# demeter_v27.net
KiCad netlist of a schematic drawn in EAGLE
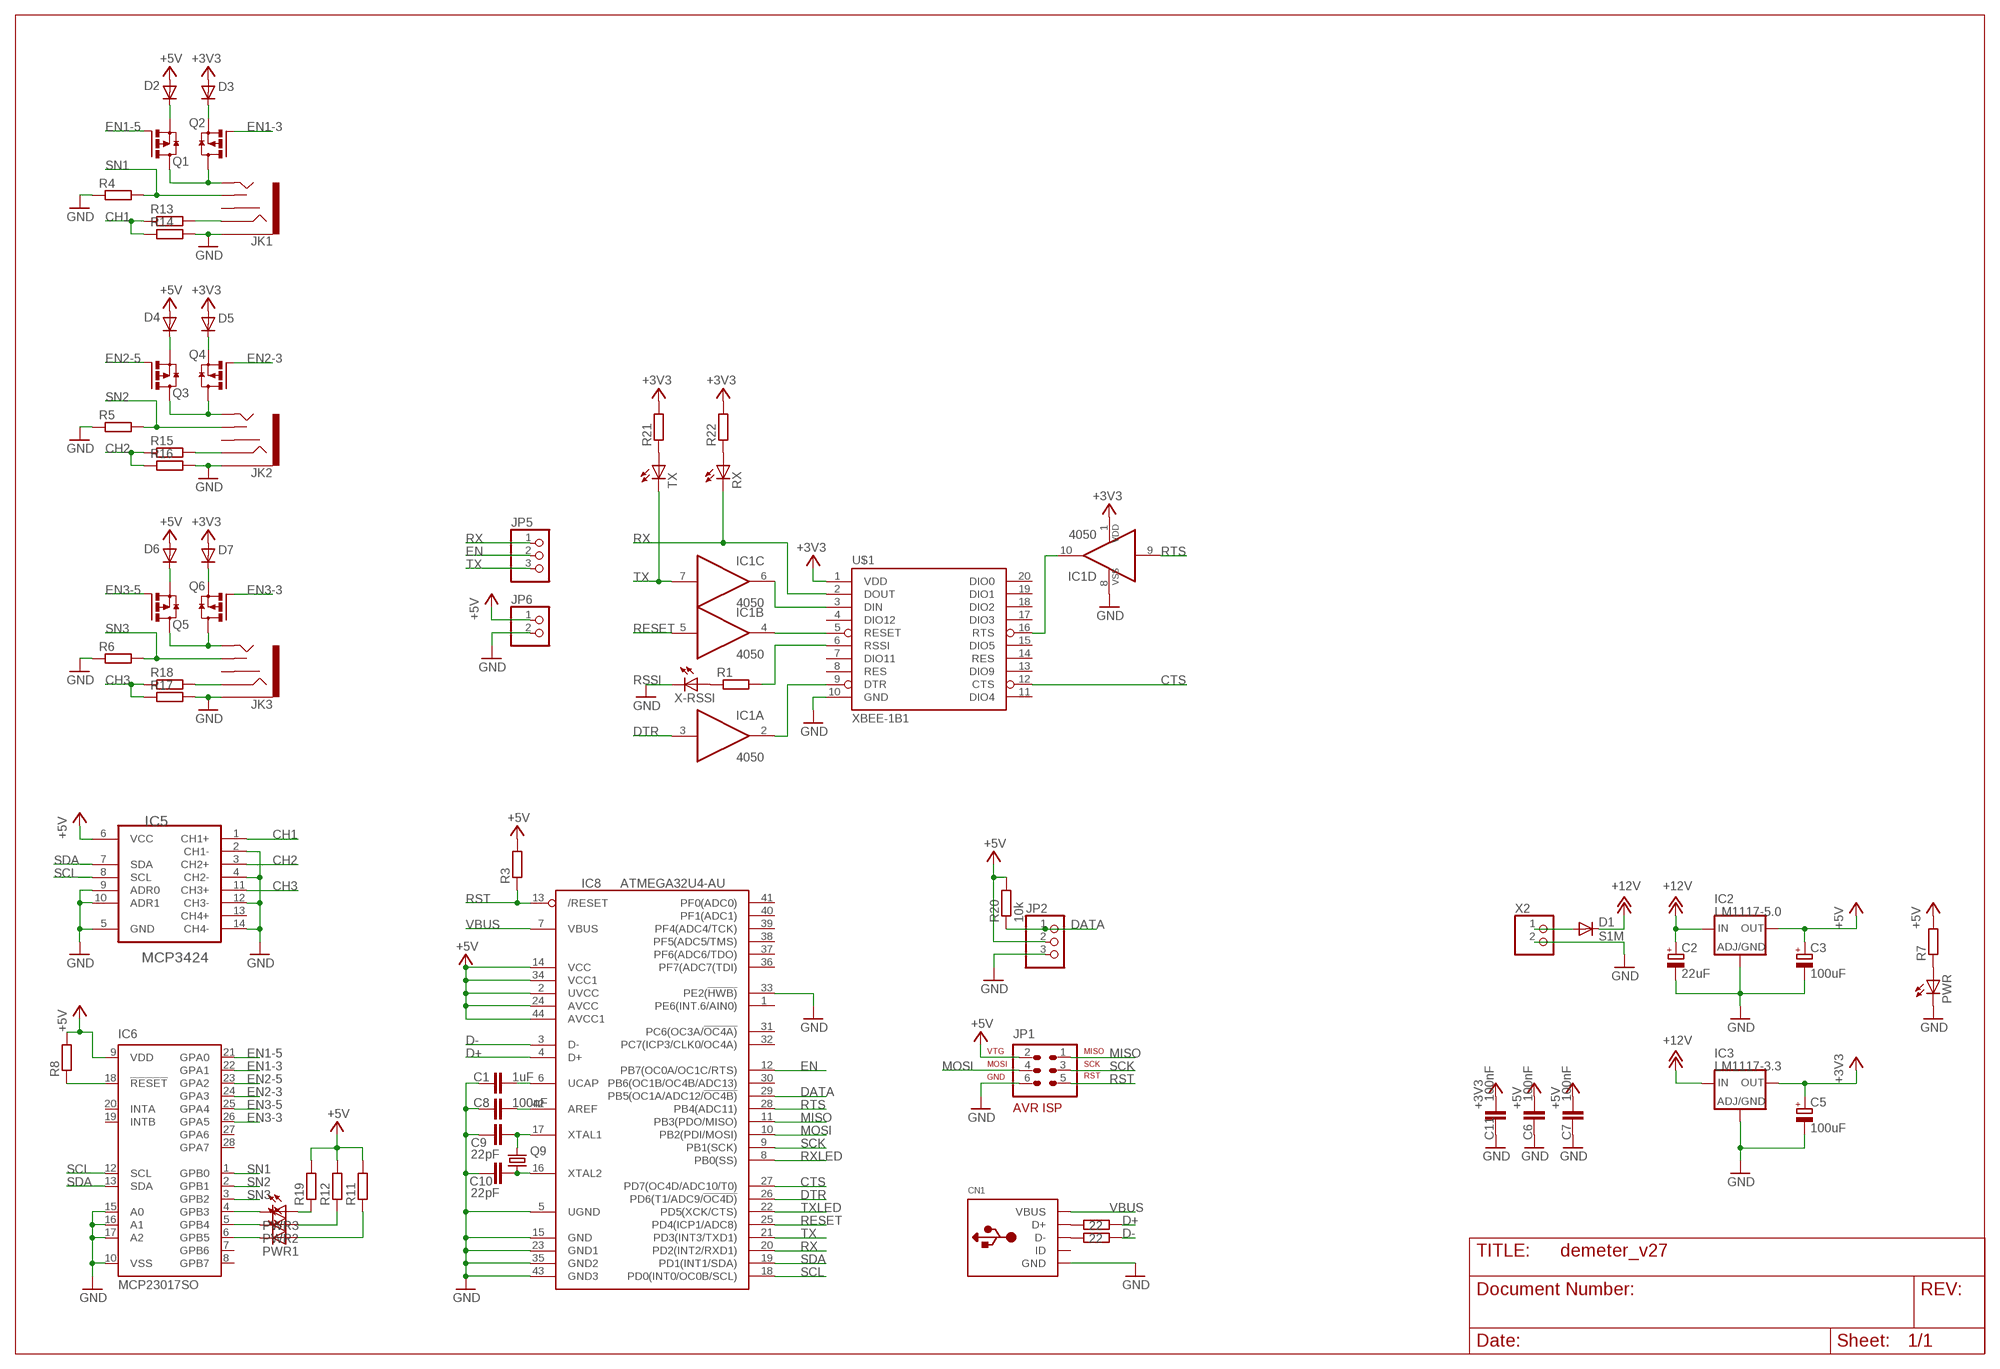
[diagram p0: schematic, sheet 1]

(export (version "E")
  (design (tool "Eeschema 10.0.6"))
  (components
    (comp (ref "C1")
      (value "1uF")
      (footprint "eagle-import:C0805K")
      (libsource (lib "eagle-import") (part "C-EUC0805K"))
    )
    (comp (ref "C2")
      (value "22uF")
      (footprint "eagle-import:PANASONIC_D")
      (libsource (lib "eagle-import") (part "CPOL-EUPD"))
    )
    (comp (ref "C3")
      (value "100uF")
      (footprint "eagle-import:PANASONIC_D")
      (libsource (lib "eagle-import") (part "CPOL-EUPD"))
    )
    (comp (ref "C5")
      (value "100uF")
      (footprint "eagle-import:PANASONIC_D")
      (libsource (lib "eagle-import") (part "CPOL-EUPD"))
    )
    (comp (ref "C6")
      (value "100nF")
      (footprint "eagle-import:C0805K")
      (libsource (lib "eagle-import") (part "C-EUC0805K"))
    )
    (comp (ref "C7")
      (value "100nF")
      (footprint "eagle-import:C0805K")
      (libsource (lib "eagle-import") (part "C-EUC0805K"))
    )
    (comp (ref "C8")
      (value "100nF")
      (footprint "eagle-import:C0805K")
      (libsource (lib "eagle-import") (part "C-EUC0805K"))
    )
    (comp (ref "C9")
      (value "22pF")
      (footprint "eagle-import:C0805K")
      (libsource (lib "eagle-import") (part "C-EUC0805K"))
    )
    (comp (ref "C10")
      (value "22pF")
      (footprint "eagle-import:C0805K")
      (libsource (lib "eagle-import") (part "C-EUC0805K"))
    )
    (comp (ref "C11")
      (value "100nF")
      (footprint "eagle-import:C0805K")
      (libsource (lib "eagle-import") (part "C-EUC0805K"))
    )
    (comp (ref "CN1")
      (value "USBMINIB")
      (footprint "eagle-import:USB-MINIB")
      (libsource (lib "eagle-import") (part "USBMINIB"))
    )
    (comp (ref "D1")
      (value "S1M")
      (footprint "eagle-import:DO-214AC")
      (libsource (lib "eagle-import") (part "S1M"))
    )
    (comp (ref "D2")
      (value "MBR0520")
      (footprint "eagle-import:SOD123")
      (libsource (lib "eagle-import") (part "MBR0520"))
    )
    (comp (ref "D3")
      (value "MBR0520")
      (footprint "eagle-import:SOD123")
      (libsource (lib "eagle-import") (part "MBR0520"))
    )
    (comp (ref "D4")
      (value "MBR0520")
      (footprint "eagle-import:SOD123")
      (libsource (lib "eagle-import") (part "MBR0520"))
    )
    (comp (ref "D5")
      (value "MBR0520")
      (footprint "eagle-import:SOD123")
      (libsource (lib "eagle-import") (part "MBR0520"))
    )
    (comp (ref "D6")
      (value "MBR0520")
      (footprint "eagle-import:SOD123")
      (libsource (lib "eagle-import") (part "MBR0520"))
    )
    (comp (ref "D7")
      (value "MBR0520")
      (footprint "eagle-import:SOD123")
      (libsource (lib "eagle-import") (part "MBR0520"))
    )
    (comp (ref "IC1")
      (value "4050")
      (footprint "eagle-import:SO16")
      (libsource (lib "eagle-import") (part "4050D"))
    )
    (comp (ref "IC2")
      (value "LM1117-5.0")
      (footprint "eagle-import:DPACK")
      (libsource (lib "eagle-import") (part "LM1117DT"))
    )
    (comp (ref "IC3")
      (value "LM1117-3.3")
      (footprint "eagle-import:DPACK")
      (libsource (lib "eagle-import") (part "LM1117DT"))
    )
    (comp (ref "IC5")
      (value "MCP3424")
      (footprint "eagle-import:SO14")
      (fields (field (name "MPN") "MCP3424-E/SL"))
      (libsource (lib "eagle-import") (part "MCP3424"))
    )
    (comp (ref "IC6")
      (value "MCP23017SO")
      (footprint "eagle-import:SO28W")
      (fields (field (name "MF") "MICROCHIP") (field (name "MPN") "MCP23017-E/SO"))
      (libsource (lib "eagle-import") (part "MCP23017SO"))
    )
    (comp (ref "IC8")
      (value "ATMEGA32U4-AU")
      (footprint "eagle-import:TQFP44")
      (libsource (lib "eagle-import") (part "ATMEGA32U4-AU"))
    )
    (comp (ref "JK1")
      (value "AUDIO-JACK2PTH")
      (footprint "eagle-import:AUDIO-JACK")
      (libsource (lib "eagle-import") (part "AUDIO-JACK2PTH"))
    )
    (comp (ref "JK2")
      (value "AUDIO-JACK2PTH")
      (footprint "eagle-import:AUDIO-JACK")
      (libsource (lib "eagle-import") (part "AUDIO-JACK2PTH"))
    )
    (comp (ref "JK3")
      (value "AUDIO-JACK2PTH")
      (footprint "eagle-import:AUDIO-JACK")
      (libsource (lib "eagle-import") (part "AUDIO-JACK2PTH"))
    )
    (comp (ref "JP1")
      (value "AVR-ISP-6")
      (footprint "eagle-import:AVR-ISP-6")
      (libsource (lib "eagle-import") (part "AVR-ISP-6"))
    )
    (comp (ref "JP2")
      (value "PINHD-1X3180")
      (footprint "eagle-import:1X03")
      (libsource (lib "eagle-import") (part "PINHD-1X3180"))
    )
    (comp (ref "JP5")
      (value "PINHD-1X3180")
      (footprint "eagle-import:1X03")
      (libsource (lib "eagle-import") (part "PINHD-1X3180"))
    )
    (comp (ref "JP6")
      (value "PINHD-1X2")
      (footprint "eagle-import:1X02")
      (libsource (lib "eagle-import") (part "PINHD-1X2"))
    )
    (comp (ref "PWR")
      (value "LED0805")
      (footprint "eagle-import:CHIP-LED0805")
      (libsource (lib "eagle-import") (part "LED0805"))
    )
    (comp (ref "PWR1")
      (value "LED0805")
      (footprint "eagle-import:CHIP-LED0805")
      (libsource (lib "eagle-import") (part "LED0805"))
    )
    (comp (ref "PWR2")
      (value "LED0805")
      (footprint "eagle-import:CHIP-LED0805")
      (libsource (lib "eagle-import") (part "LED0805"))
    )
    (comp (ref "PWR3")
      (value "LED0805")
      (footprint "eagle-import:CHIP-LED0805")
      (libsource (lib "eagle-import") (part "LED0805"))
    )
    (comp (ref "Q1")
      (value "IRLML6402")
      (footprint "eagle-import:SOT23")
      (libsource (lib "eagle-import") (part "IRLML6402"))
    )
    (comp (ref "Q2")
      (value "IRLML6402")
      (footprint "eagle-import:SOT23")
      (libsource (lib "eagle-import") (part "IRLML6402"))
    )
    (comp (ref "Q3")
      (value "IRLML6402")
      (footprint "eagle-import:SOT23")
      (libsource (lib "eagle-import") (part "IRLML6402"))
    )
    (comp (ref "Q4")
      (value "IRLML6402")
      (footprint "eagle-import:SOT23")
      (libsource (lib "eagle-import") (part "IRLML6402"))
    )
    (comp (ref "Q5")
      (value "IRLML6402")
      (footprint "eagle-import:SOT23")
      (libsource (lib "eagle-import") (part "IRLML6402"))
    )
    (comp (ref "Q6")
      (value "IRLML6402")
      (footprint "eagle-import:SOT23")
      (libsource (lib "eagle-import") (part "IRLML6402"))
    )
    (comp (ref "Q9")
      (value "CRYSTALHC49UP")
      (footprint "eagle-import:HC49UP")
      (libsource (lib "eagle-import") (part "CRYSTALHC49UP"))
    )
    (comp (ref "R1")
      (value "R-EU_R0805")
      (footprint "eagle-import:R0805")
      (libsource (lib "eagle-import") (part "R-EU_R0805"))
    )
    (comp (ref "R3")
      (value "R-EU_R0805")
      (footprint "eagle-import:R0805")
      (libsource (lib "eagle-import") (part "R-EU_R0805"))
    )
    (comp (ref "R4")
      (value "R-EU_R0805")
      (footprint "eagle-import:R0805")
      (libsource (lib "eagle-import") (part "R-EU_R0805"))
    )
    (comp (ref "R5")
      (value "R-EU_R0805")
      (footprint "eagle-import:R0805")
      (libsource (lib "eagle-import") (part "R-EU_R0805"))
    )
    (comp (ref "R6")
      (value "R-EU_R0805")
      (footprint "eagle-import:R0805")
      (libsource (lib "eagle-import") (part "R-EU_R0805"))
    )
    (comp (ref "R7")
      (value "R-EU_R0805")
      (footprint "eagle-import:R0805")
      (libsource (lib "eagle-import") (part "R-EU_R0805"))
    )
    (comp (ref "R8")
      (value "R-EU_R0805")
      (footprint "eagle-import:R0805")
      (libsource (lib "eagle-import") (part "R-EU_R0805"))
    )
    (comp (ref "R9")
      (value "22")
      (footprint "eagle-import:R0805")
      (libsource (lib "eagle-import") (part "R-EU_R0805"))
    )
    (comp (ref "R10")
      (value "22")
      (footprint "eagle-import:R0805")
      (libsource (lib "eagle-import") (part "R-EU_R0805"))
    )
    (comp (ref "R11")
      (value "R-EU_R0805")
      (footprint "eagle-import:R0805")
      (libsource (lib "eagle-import") (part "R-EU_R0805"))
    )
    (comp (ref "R12")
      (value "R-EU_R0805")
      (footprint "eagle-import:R0805")
      (libsource (lib "eagle-import") (part "R-EU_R0805"))
    )
    (comp (ref "R13")
      (value "R-EU_R0805")
      (footprint "eagle-import:R0805")
      (libsource (lib "eagle-import") (part "R-EU_R0805"))
    )
    (comp (ref "R14")
      (value "R-EU_R0805")
      (footprint "eagle-import:R0805")
      (libsource (lib "eagle-import") (part "R-EU_R0805"))
    )
    (comp (ref "R15")
      (value "R-EU_R0805")
      (footprint "eagle-import:R0805")
      (libsource (lib "eagle-import") (part "R-EU_R0805"))
    )
    (comp (ref "R16")
      (value "R-EU_R0805")
      (footprint "eagle-import:R0805")
      (libsource (lib "eagle-import") (part "R-EU_R0805"))
    )
    (comp (ref "R17")
      (value "R-EU_R0805")
      (footprint "eagle-import:R0805")
      (libsource (lib "eagle-import") (part "R-EU_R0805"))
    )
    (comp (ref "R18")
      (value "R-EU_R0805")
      (footprint "eagle-import:R0805")
      (libsource (lib "eagle-import") (part "R-EU_R0805"))
    )
    (comp (ref "R19")
      (value "R-EU_R0805")
      (footprint "eagle-import:R0805")
      (libsource (lib "eagle-import") (part "R-EU_R0805"))
    )
    (comp (ref "R20")
      (value "10k")
      (footprint "eagle-import:R0805")
      (libsource (lib "eagle-import") (part "R-EU_R0805"))
    )
    (comp (ref "R21")
      (value "R-EU_R0805")
      (footprint "eagle-import:R0805")
      (libsource (lib "eagle-import") (part "R-EU_R0805"))
    )
    (comp (ref "R22")
      (value "R-EU_R0805")
      (footprint "eagle-import:R0805")
      (libsource (lib "eagle-import") (part "R-EU_R0805"))
    )
    (comp (ref "RX")
      (value "LED0805")
      (footprint "eagle-import:CHIP-LED0805")
      (libsource (lib "eagle-import") (part "LED0805"))
    )
    (comp (ref "TX")
      (value "LED0805")
      (footprint "eagle-import:CHIP-LED0805")
      (libsource (lib "eagle-import") (part "LED0805"))
    )
    (comp (ref "U$1")
      (value "XBEE-1B1")
      (footprint "eagle-import:XBEE-1")
      (libsource (lib "eagle-import") (part "XBEE-1B1"))
    )
    (comp (ref "X-RSSI")
      (value "LED0805")
      (footprint "eagle-import:CHIP-LED0805")
      (libsource (lib "eagle-import") (part "LED0805"))
    )
    (comp (ref "X2")
      (value "W237-102")
      (footprint "eagle-import:W237-102")
      (libsource (lib "eagle-import") (part "W237-102"))
    )
  )
  (nets
    (net (code "1") (name "+3V3") (class "Default")
      (node (ref "C11") (pin "1") (pinfunction "1_1") (pintype "passive"))
      (node (ref "C5") (pin "+") (pinfunction "+_+") (pintype "passive"))
      (node (ref "D3") (pin "A") (pinfunction "A_A") (pintype "passive"))
      (node (ref "D5") (pin "A") (pinfunction "A_A") (pintype "passive"))
      (node (ref "D7") (pin "A") (pinfunction "A_A") (pintype "passive"))
      (node (ref "IC1") (pin "1") (pinfunction "VDD_1") (pintype "power_in"))
      (node (ref "IC3") (pin "4") (pinfunction "OUT_4") (pintype "passive"))
      (node (ref "R21") (pin "2") (pinfunction "2_2") (pintype "passive"))
      (node (ref "R22") (pin "2") (pinfunction "2_2") (pintype "passive"))
      (node (ref "U$1") (pin "1") (pinfunction "VDD_1") (pintype "power_in"))
    )
    (net (code "2") (name "+5V") (class "Default")
      (node (ref "C3") (pin "+") (pinfunction "+_+") (pintype "passive"))
      (node (ref "C6") (pin "1") (pinfunction "1_1") (pintype "passive"))
      (node (ref "C7") (pin "1") (pinfunction "1_1") (pintype "passive"))
      (node (ref "D2") (pin "A") (pinfunction "A_A") (pintype "passive"))
      (node (ref "D4") (pin "A") (pinfunction "A_A") (pintype "passive"))
      (node (ref "D6") (pin "A") (pinfunction "A_A") (pintype "passive"))
      (node (ref "IC2") (pin "4") (pinfunction "OUT_4") (pintype "passive"))
      (node (ref "IC5") (pin "6") (pinfunction "VCC_6") (pintype "power_in"))
      (node (ref "IC6") (pin "9") (pinfunction "VDD_9") (pintype "power_in"))
      (node (ref "IC8") (pin "14") (pinfunction "VCC_14") (pintype "bidirectional"))
      (node (ref "IC8") (pin "2") (pinfunction "UVCC_2") (pintype "bidirectional"))
      (node (ref "IC8") (pin "24") (pinfunction "AVCC_24") (pintype "bidirectional"))
      (node (ref "IC8") (pin "34") (pinfunction "VCC1_34") (pintype "bidirectional"))
      (node (ref "IC8") (pin "44") (pinfunction "AVCC1_44") (pintype "bidirectional"))
      (node (ref "JP1") (pin "2") (pinfunction "VTG_2") (pintype "passive"))
      (node (ref "JP2") (pin "2") (pinfunction "2_2") (pintype "passive"))
      (node (ref "JP6") (pin "1") (pinfunction "1_1") (pintype "passive"))
      (node (ref "R11") (pin "2") (pinfunction "2_2") (pintype "passive"))
      (node (ref "R12") (pin "2") (pinfunction "2_2") (pintype "passive"))
      (node (ref "R19") (pin "2") (pinfunction "2_2") (pintype "passive"))
      (node (ref "R20") (pin "2") (pinfunction "2_2") (pintype "passive"))
      (node (ref "R3") (pin "2") (pinfunction "2_2") (pintype "passive"))
      (node (ref "R7") (pin "2") (pinfunction "2_2") (pintype "passive"))
      (node (ref "R8") (pin "2") (pinfunction "2_2") (pintype "passive"))
    )
    (net (code "3") (name "+12V") (class "Default")
      (node (ref "C2") (pin "+") (pinfunction "+_+") (pintype "passive"))
      (node (ref "D1") (pin "C") (pinfunction "C_C") (pintype "passive"))
      (node (ref "IC2") (pin "3") (pinfunction "IN_3") (pintype "input"))
      (node (ref "IC3") (pin "3") (pinfunction "IN_3") (pintype "input"))
    )
    (net (code "4") (name "/CH1") (class "Default")
      (node (ref "IC5") (pin "1") (pinfunction "CH1+_1") (pintype "input"))
      (node (ref "R13") (pin "1") (pinfunction "1_1") (pintype "passive"))
      (node (ref "R14") (pin "1") (pinfunction "1_1") (pintype "passive"))
    )
    (net (code "5") (name "/CH2") (class "Default")
      (node (ref "IC5") (pin "3") (pinfunction "CH2+_3") (pintype "input"))
      (node (ref "R15") (pin "1") (pinfunction "1_1") (pintype "passive"))
      (node (ref "R16") (pin "1") (pinfunction "1_1") (pintype "passive"))
    )
    (net (code "6") (name "/CH3") (class "Default")
      (node (ref "IC5") (pin "11") (pinfunction "CH3+_11") (pintype "input"))
      (node (ref "R17") (pin "1") (pinfunction "1_1") (pintype "passive"))
      (node (ref "R18") (pin "1") (pinfunction "1_1") (pintype "passive"))
    )
    (net (code "7") (name "/CTS") (class "Default")
      (node (ref "IC8") (pin "27") (pinfunction "PD7(OC4D/ADC10/T0)_27") (pintype "bidirectional"))
      (node (ref "U$1") (pin "12") (pinfunction "CTS_12") (pintype "output"))
    )
    (net (code "8") (name "/D+") (class "Default")
      (node (ref "IC8") (pin "4") (pinfunction "D+_4") (pintype "bidirectional"))
      (node (ref "R9") (pin "1") (pinfunction "1_1") (pintype "passive"))
    )
    (net (code "9") (name "/D-") (class "Default")
      (node (ref "IC8") (pin "3") (pinfunction "D-_3") (pintype "bidirectional"))
      (node (ref "R10") (pin "1") (pinfunction "1_1") (pintype "passive"))
    )
    (net (code "10") (name "/DATA") (class "Default")
      (node (ref "IC8") (pin "29") (pinfunction "PB5(OC1A/ADC12/~{OC4B})_29") (pintype "bidirectional"))
      (node (ref "JP2") (pin "1") (pinfunction "1_1") (pintype "passive"))
      (node (ref "R20") (pin "1") (pinfunction "1_1") (pintype "passive"))
    )
    (net (code "11") (name "/DTR") (class "Default")
      (node (ref "IC1") (pin "3") (pinfunction "I_3") (pintype "input"))
      (node (ref "IC8") (pin "26") (pinfunction "PD6(T1/ADC9/~{OC4D})_26") (pintype "bidirectional"))
    )
    (net (code "12") (name "/EN") (class "Default")
      (node (ref "IC8") (pin "12") (pinfunction "PB7(OC0A/OC1C/RTS)_12") (pintype "bidirectional"))
      (node (ref "JP5") (pin "2") (pinfunction "2_2") (pintype "passive"))
    )
    (net (code "13") (name "/EN1-3") (class "Default")
      (node (ref "IC6") (pin "22") (pinfunction "GPA1_22") (pintype "bidirectional"))
      (node (ref "Q2") (pin "1") (pinfunction "G_1") (pintype "passive"))
    )
    (net (code "14") (name "/EN1-5") (class "Default")
      (node (ref "IC6") (pin "21") (pinfunction "GPA0_21") (pintype "bidirectional"))
      (node (ref "Q1") (pin "1") (pinfunction "G_1") (pintype "passive"))
    )
    (net (code "15") (name "/EN2-3") (class "Default")
      (node (ref "IC6") (pin "24") (pinfunction "GPA3_24") (pintype "bidirectional"))
      (node (ref "Q4") (pin "1") (pinfunction "G_1") (pintype "passive"))
    )
    (net (code "16") (name "/EN2-5") (class "Default")
      (node (ref "IC6") (pin "23") (pinfunction "GPA2_23") (pintype "bidirectional"))
      (node (ref "Q3") (pin "1") (pinfunction "G_1") (pintype "passive"))
    )
    (net (code "17") (name "/EN3-3") (class "Default")
      (node (ref "IC6") (pin "26") (pinfunction "GPA5_26") (pintype "bidirectional"))
      (node (ref "Q6") (pin "1") (pinfunction "G_1") (pintype "passive"))
    )
    (net (code "18") (name "/EN3-5") (class "Default")
      (node (ref "IC6") (pin "25") (pinfunction "GPA4_25") (pintype "bidirectional"))
      (node (ref "Q5") (pin "1") (pinfunction "G_1") (pintype "passive"))
    )
    (net (code "19") (name "/MISO") (class "Default")
      (node (ref "IC8") (pin "11") (pinfunction "PB3(PDO/MISO)_11") (pintype "bidirectional"))
      (node (ref "JP1") (pin "1") (pinfunction "MISO_1") (pintype "passive"))
    )
    (net (code "20") (name "/MOSI") (class "Default")
      (node (ref "IC8") (pin "10") (pinfunction "PB2(PDI/MOSI)_10") (pintype "bidirectional"))
      (node (ref "JP1") (pin "4") (pinfunction "MOSI_4") (pintype "passive"))
    )
    (net (code "21") (name "/RESET") (class "Default")
      (node (ref "IC1") (pin "5") (pinfunction "I_5") (pintype "input"))
      (node (ref "IC8") (pin "25") (pinfunction "PD4(ICP1/ADC8)_25") (pintype "bidirectional"))
    )
    (net (code "22") (name "/RSSI") (class "Default")
      (node (ref "R1") (pin "2") (pinfunction "2_2") (pintype "passive"))
      (node (ref "U$1") (pin "6") (pinfunction "RSSI_6") (pintype "bidirectional"))
    )
    (net (code "23") (name "/RST") (class "Default")
      (node (ref "IC8") (pin "13") (pinfunction "/RESET_13") (pintype "bidirectional"))
      (node (ref "JP1") (pin "5") (pinfunction "RST_5") (pintype "passive"))
      (node (ref "R3") (pin "1") (pinfunction "1_1") (pintype "passive"))
    )
    (net (code "24") (name "/RTS") (class "Default")
      (node (ref "IC1") (pin "9") (pinfunction "I_9") (pintype "input"))
      (node (ref "IC8") (pin "28") (pinfunction "PB4(ADC11)_28") (pintype "bidirectional"))
    )
    (net (code "25") (name "/RX") (class "Default")
      (node (ref "IC8") (pin "20") (pinfunction "PD2(INT2/RXD1)_20") (pintype "bidirectional"))
      (node (ref "JP5") (pin "1") (pinfunction "1_1") (pintype "passive"))
      (node (ref "RX") (pin "C") (pinfunction "C_C") (pintype "passive"))
      (node (ref "U$1") (pin "2") (pinfunction "DOUT_2") (pintype "output"))
    )
    (net (code "26") (name "/RXLED") (class "Default")
      (node (ref "IC8") (pin "8") (pinfunction "PB0(SS)_8") (pintype "bidirectional"))
    )
    (net (code "27") (name "/SCK") (class "Default")
      (node (ref "IC8") (pin "9") (pinfunction "PB1(SCK)_9") (pintype "bidirectional"))
      (node (ref "JP1") (pin "3") (pinfunction "SCK_3") (pintype "passive"))
    )
    (net (code "28") (name "/SCL") (class "Default")
      (node (ref "IC5") (pin "8") (pinfunction "SCL_8") (pintype "input"))
      (node (ref "IC6") (pin "12") (pinfunction "SCL_12") (pintype "input"))
      (node (ref "IC8") (pin "18") (pinfunction "PD0(INT0/OC0B/SCL)_18") (pintype "bidirectional"))
    )
    (net (code "29") (name "/SDA") (class "Default")
      (node (ref "IC5") (pin "7") (pinfunction "SDA_7") (pintype "bidirectional"))
      (node (ref "IC6") (pin "13") (pinfunction "SDA_13") (pintype "bidirectional"))
      (node (ref "IC8") (pin "19") (pinfunction "PD1(INT1/SDA)_19") (pintype "bidirectional"))
    )
    (net (code "30") (name "/SN1") (class "Default")
      (node (ref "IC6") (pin "1") (pinfunction "GPB0_1") (pintype "bidirectional"))
      (node (ref "JK1") (pin "TSH") (pinfunction "TSH_TSH") (pintype "bidirectional"))
      (node (ref "R4") (pin "2") (pinfunction "2_2") (pintype "passive"))
    )
    (net (code "31") (name "/SN2") (class "Default")
      (node (ref "IC6") (pin "2") (pinfunction "GPB1_2") (pintype "bidirectional"))
      (node (ref "JK2") (pin "TSH") (pinfunction "TSH_TSH") (pintype "bidirectional"))
      (node (ref "R5") (pin "2") (pinfunction "2_2") (pintype "passive"))
    )
    (net (code "32") (name "/SN3") (class "Default")
      (node (ref "IC6") (pin "3") (pinfunction "GPB2_3") (pintype "bidirectional"))
      (node (ref "JK3") (pin "TSH") (pinfunction "TSH_TSH") (pintype "bidirectional"))
      (node (ref "R6") (pin "2") (pinfunction "2_2") (pintype "passive"))
    )
    (net (code "33") (name "/TX") (class "Default")
      (node (ref "IC1") (pin "7") (pinfunction "I_7") (pintype "input"))
      (node (ref "IC8") (pin "21") (pinfunction "PD3(INT3/TXD1)_21") (pintype "bidirectional"))
      (node (ref "JP5") (pin "3") (pinfunction "3_3") (pintype "passive"))
      (node (ref "TX") (pin "C") (pinfunction "C_C") (pintype "passive"))
    )
    (net (code "34") (name "/TXLED") (class "Default")
      (node (ref "IC8") (pin "22") (pinfunction "PD5(XCK/CTS)_22") (pintype "bidirectional"))
    )
    (net (code "35") (name "/VBUS") (class "Default")
      (node (ref "CN1") (pin "VBUS") (pinfunction "VBUS_VBUS") (pintype "power_in"))
      (node (ref "IC8") (pin "7") (pinfunction "VBUS_7") (pintype "bidirectional"))
    )
    (net (code "36") (name "GND") (class "Default")
      (node (ref "C1") (pin "2") (pinfunction "2_2") (pintype "passive"))
      (node (ref "C10") (pin "2") (pinfunction "2_2") (pintype "passive"))
      (node (ref "C11") (pin "2") (pinfunction "2_2") (pintype "passive"))
      (node (ref "C2") (pin "-") (pinfunction "-_-") (pintype "passive"))
      (node (ref "C3") (pin "-") (pinfunction "-_-") (pintype "passive"))
      (node (ref "C5") (pin "-") (pinfunction "-_-") (pintype "passive"))
      (node (ref "C6") (pin "2") (pinfunction "2_2") (pintype "passive"))
      (node (ref "C7") (pin "2") (pinfunction "2_2") (pintype "passive"))
      (node (ref "C8") (pin "2") (pinfunction "2_2") (pintype "passive"))
      (node (ref "C9") (pin "2") (pinfunction "2_2") (pintype "passive"))
      (node (ref "CN1") (pin "GND") (pinfunction "GND_GND") (pintype "power_in"))
      (node (ref "IC1") (pin "8") (pinfunction "VSS_8") (pintype "power_in"))
      (node (ref "IC2") (pin "1") (pinfunction "ADJ_1") (pintype "input"))
      (node (ref "IC3") (pin "1") (pinfunction "ADJ_1") (pintype "input"))
      (node (ref "IC5") (pin "10") (pinfunction "ADR1_10") (pintype "input"))
      (node (ref "IC5") (pin "12") (pinfunction "CH3-_12") (pintype "input"))
      (node (ref "IC5") (pin "14") (pinfunction "CH4-_14") (pintype "input"))
      (node (ref "IC5") (pin "2") (pinfunction "CH1-_2") (pintype "input"))
      (node (ref "IC5") (pin "4") (pinfunction "CH2-_4") (pintype "input"))
      (node (ref "IC5") (pin "5") (pinfunction "GND_5") (pintype "power_in"))
      (node (ref "IC5") (pin "9") (pinfunction "ADR0_9") (pintype "input"))
      (node (ref "IC6") (pin "10") (pinfunction "VSS_10") (pintype "power_in"))
      (node (ref "IC6") (pin "15") (pinfunction "A0_15") (pintype "input"))
      (node (ref "IC6") (pin "16") (pinfunction "A1_16") (pintype "input"))
      (node (ref "IC6") (pin "17") (pinfunction "A2_17") (pintype "input"))
      (node (ref "IC8") (pin "15") (pinfunction "GND_15") (pintype "bidirectional"))
      (node (ref "IC8") (pin "23") (pinfunction "GND1_23") (pintype "bidirectional"))
      (node (ref "IC8") (pin "33") (pinfunction "PE2(~{HWB})_33") (pintype "bidirectional"))
      (node (ref "IC8") (pin "35") (pinfunction "GND2_35") (pintype "bidirectional"))
      (node (ref "IC8") (pin "43") (pinfunction "GND3_43") (pintype "bidirectional"))
      (node (ref "IC8") (pin "5") (pinfunction "UGND_5") (pintype "bidirectional"))
      (node (ref "JK1") (pin "SLEEVE") (pinfunction "SLEEVE_SLEEVE") (pintype "bidirectional"))
      (node (ref "JK2") (pin "SLEEVE") (pinfunction "SLEEVE_SLEEVE") (pintype "bidirectional"))
      (node (ref "JK3") (pin "SLEEVE") (pinfunction "SLEEVE_SLEEVE") (pintype "bidirectional"))
      (node (ref "JP1") (pin "6") (pinfunction "GND_6") (pintype "passive"))
      (node (ref "JP2") (pin "3") (pinfunction "3_3") (pintype "passive"))
      (node (ref "JP6") (pin "2") (pinfunction "2_2") (pintype "passive"))
      (node (ref "PWR") (pin "C") (pinfunction "C_C") (pintype "passive"))
      (node (ref "R14") (pin "2") (pinfunction "2_2") (pintype "passive"))
      (node (ref "R16") (pin "2") (pinfunction "2_2") (pintype "passive"))
      (node (ref "R17") (pin "2") (pinfunction "2_2") (pintype "passive"))
      (node (ref "R4") (pin "1") (pinfunction "1_1") (pintype "passive"))
      (node (ref "R5") (pin "1") (pinfunction "1_1") (pintype "passive"))
      (node (ref "R6") (pin "1") (pinfunction "1_1") (pintype "passive"))
      (node (ref "U$1") (pin "10") (pinfunction "GND_10") (pintype "power_in"))
      (node (ref "X-RSSI") (pin "C") (pinfunction "C_C") (pintype "passive"))
      (node (ref "X2") (pin "2") (pinfunction "2_2") (pintype "passive"))
    )
    (net (code "37") (name "Net-(CN1-PadD+)") (class "Default")
      (node (ref "CN1") (pin "D+") (pinfunction "D+_D+") (pintype "bidirectional"))
      (node (ref "R9") (pin "2") (pinfunction "2_2") (pintype "passive"))
    )
    (net (code "38") (name "Net-(CN1-PadD-)") (class "Default")
      (node (ref "CN1") (pin "D-") (pinfunction "D-_D-") (pintype "bidirectional"))
      (node (ref "R10") (pin "2") (pinfunction "2_2") (pintype "passive"))
    )
    (net (code "39") (name "Net-(D1-PadA)") (class "Default")
      (node (ref "D1") (pin "A") (pinfunction "A_A") (pintype "passive"))
      (node (ref "X2") (pin "1") (pinfunction "1_1") (pintype "passive"))
    )
    (net (code "40") (name "Net-(IC1A-O)") (class "Default")
      (node (ref "IC1") (pin "2") (pinfunction "O_2") (pintype "output"))
      (node (ref "U$1") (pin "9") (pinfunction "DTR_9") (pintype "bidirectional"))
    )
    (net (code "41") (name "Net-(IC1B-O)") (class "Default")
      (node (ref "IC1") (pin "4") (pinfunction "O_4") (pintype "output"))
      (node (ref "U$1") (pin "5") (pinfunction "RESET_5") (pintype "input"))
    )
    (net (code "42") (name "Net-(IC1C-O)") (class "Default")
      (node (ref "IC1") (pin "6") (pinfunction "O_6") (pintype "output"))
      (node (ref "U$1") (pin "3") (pinfunction "DIN_3") (pintype "input"))
    )
    (net (code "43") (name "Net-(IC1D-O)") (class "Default")
      (node (ref "IC1") (pin "10") (pinfunction "O_10") (pintype "output"))
      (node (ref "U$1") (pin "16") (pinfunction "RTS_16") (pintype "input"))
    )
    (net (code "44") (name "Net-(IC6-GPB3)") (class "Default")
      (node (ref "IC6") (pin "4") (pinfunction "GPB3_4") (pintype "bidirectional"))
      (node (ref "PWR3") (pin "C") (pinfunction "C_C") (pintype "passive"))
    )
    (net (code "45") (name "Net-(IC6-GPB4)") (class "Default")
      (node (ref "IC6") (pin "5") (pinfunction "GPB4_5") (pintype "bidirectional"))
      (node (ref "PWR2") (pin "C") (pinfunction "C_C") (pintype "passive"))
    )
    (net (code "46") (name "Net-(IC6-GPB5)") (class "Default")
      (node (ref "IC6") (pin "6") (pinfunction "GPB5_6") (pintype "bidirectional"))
      (node (ref "PWR1") (pin "C") (pinfunction "C_C") (pintype "passive"))
    )
    (net (code "47") (name "Net-(IC6-~{RESET})") (class "Default")
      (node (ref "IC6") (pin "18") (pinfunction "~{RESET}_18") (pintype "input"))
      (node (ref "R8") (pin "1") (pinfunction "1_1") (pintype "passive"))
    )
    (net (code "48") (name "Net-(IC8-AREF)") (class "Default")
      (node (ref "C8") (pin "1") (pinfunction "1_1") (pintype "passive"))
      (node (ref "IC8") (pin "42") (pinfunction "AREF_42") (pintype "bidirectional"))
    )
    (net (code "49") (name "Net-(IC8-UCAP)") (class "Default")
      (node (ref "C1") (pin "1") (pinfunction "1_1") (pintype "passive"))
      (node (ref "IC8") (pin "6") (pinfunction "UCAP_6") (pintype "bidirectional"))
    )
    (net (code "50") (name "Net-(IC8-XTAL1)") (class "Default")
      (node (ref "C9") (pin "1") (pinfunction "1_1") (pintype "passive"))
      (node (ref "IC8") (pin "17") (pinfunction "XTAL1_17") (pintype "bidirectional"))
      (node (ref "Q9") (pin "2") (pinfunction "2_2") (pintype "passive"))
    )
    (net (code "51") (name "Net-(IC8-XTAL2)") (class "Default")
      (node (ref "C10") (pin "1") (pinfunction "1_1") (pintype "passive"))
      (node (ref "IC8") (pin "16") (pinfunction "XTAL2_16") (pintype "bidirectional"))
      (node (ref "Q9") (pin "1") (pinfunction "1_1") (pintype "passive"))
    )
    (net (code "52") (name "Net-(JK1-PadRING)") (class "Default")
      (node (ref "JK1") (pin "RING") (pinfunction "RING_RING") (pintype "bidirectional"))
      (node (ref "R13") (pin "2") (pinfunction "2_2") (pintype "passive"))
    )
    (net (code "53") (name "Net-(JK2-PadRING)") (class "Default")
      (node (ref "JK2") (pin "RING") (pinfunction "RING_RING") (pintype "bidirectional"))
      (node (ref "R15") (pin "2") (pinfunction "2_2") (pintype "passive"))
    )
    (net (code "54") (name "Net-(JK3-PadRING)") (class "Default")
      (node (ref "JK3") (pin "RING") (pinfunction "RING_RING") (pintype "bidirectional"))
      (node (ref "R18") (pin "2") (pinfunction "2_2") (pintype "passive"))
    )
    (net (code "55") (name "Net-(PWR-PadA)") (class "Default")
      (node (ref "PWR") (pin "A") (pinfunction "A_A") (pintype "passive"))
      (node (ref "R7") (pin "1") (pinfunction "1_1") (pintype "passive"))
    )
    (net (code "56") (name "Net-(PWR1-PadA)") (class "Default")
      (node (ref "PWR1") (pin "A") (pinfunction "A_A") (pintype "passive"))
      (node (ref "R11") (pin "1") (pinfunction "1_1") (pintype "passive"))
    )
    (net (code "57") (name "Net-(PWR2-PadA)") (class "Default")
      (node (ref "PWR2") (pin "A") (pinfunction "A_A") (pintype "passive"))
      (node (ref "R12") (pin "1") (pinfunction "1_1") (pintype "passive"))
    )
    (net (code "58") (name "Net-(PWR3-PadA)") (class "Default")
      (node (ref "PWR3") (pin "A") (pinfunction "A_A") (pintype "passive"))
      (node (ref "R19") (pin "1") (pinfunction "1_1") (pintype "passive"))
    )
    (net (code "59") (name "Net-(Q1-D)") (class "Default")
      (node (ref "JK1") (pin "TIP") (pinfunction "TIP_TIP") (pintype "bidirectional"))
      (node (ref "Q1") (pin "3") (pinfunction "D_3") (pintype "passive"))
      (node (ref "Q2") (pin "3") (pinfunction "D_3") (pintype "passive"))
    )
    (net (code "60") (name "Net-(Q1-S)") (class "Default")
      (node (ref "D2") (pin "C") (pinfunction "C_C") (pintype "passive"))
      (node (ref "Q1") (pin "2") (pinfunction "S_2") (pintype "passive"))
    )
    (net (code "61") (name "Net-(Q2-S)") (class "Default")
      (node (ref "D3") (pin "C") (pinfunction "C_C") (pintype "passive"))
      (node (ref "Q2") (pin "2") (pinfunction "S_2") (pintype "passive"))
    )
    (net (code "62") (name "Net-(Q3-D)") (class "Default")
      (node (ref "JK2") (pin "TIP") (pinfunction "TIP_TIP") (pintype "bidirectional"))
      (node (ref "Q3") (pin "3") (pinfunction "D_3") (pintype "passive"))
      (node (ref "Q4") (pin "3") (pinfunction "D_3") (pintype "passive"))
    )
    (net (code "63") (name "Net-(Q3-S)") (class "Default")
      (node (ref "D4") (pin "C") (pinfunction "C_C") (pintype "passive"))
      (node (ref "Q3") (pin "2") (pinfunction "S_2") (pintype "passive"))
    )
    (net (code "64") (name "Net-(Q4-S)") (class "Default")
      (node (ref "D5") (pin "C") (pinfunction "C_C") (pintype "passive"))
      (node (ref "Q4") (pin "2") (pinfunction "S_2") (pintype "passive"))
    )
    (net (code "65") (name "Net-(Q5-D)") (class "Default")
      (node (ref "JK3") (pin "TIP") (pinfunction "TIP_TIP") (pintype "bidirectional"))
      (node (ref "Q5") (pin "3") (pinfunction "D_3") (pintype "passive"))
      (node (ref "Q6") (pin "3") (pinfunction "D_3") (pintype "passive"))
    )
    (net (code "66") (name "Net-(Q5-S)") (class "Default")
      (node (ref "D6") (pin "C") (pinfunction "C_C") (pintype "passive"))
      (node (ref "Q5") (pin "2") (pinfunction "S_2") (pintype "passive"))
    )
    (net (code "67") (name "Net-(Q6-S)") (class "Default")
      (node (ref "D7") (pin "C") (pinfunction "C_C") (pintype "passive"))
      (node (ref "Q6") (pin "2") (pinfunction "S_2") (pintype "passive"))
    )
    (net (code "68") (name "Net-(R1-Pad1)") (class "Default")
      (node (ref "R1") (pin "1") (pinfunction "1_1") (pintype "passive"))
      (node (ref "X-RSSI") (pin "A") (pinfunction "A_A") (pintype "passive"))
    )
    (net (code "69") (name "Net-(R21-Pad1)") (class "Default")
      (node (ref "R21") (pin "1") (pinfunction "1_1") (pintype "passive"))
      (node (ref "TX") (pin "A") (pinfunction "A_A") (pintype "passive"))
    )
    (net (code "70") (name "Net-(R22-Pad1)") (class "Default")
      (node (ref "R22") (pin "1") (pinfunction "1_1") (pintype "passive"))
      (node (ref "RX") (pin "A") (pinfunction "A_A") (pintype "passive"))
    )
    (net (code "71") (name "unconnected-(CN1-PadID)") (class "Default")
      (node (ref "CN1") (pin "ID") (pinfunction "ID_ID") (pintype "bidirectional"))
    )
    (net (code "72") (name "unconnected-(IC5-CH4+-Pad13)") (class "Default")
      (node (ref "IC5") (pin "13") (pinfunction "CH4+_13") (pintype "input"))
    )
    (net (code "73") (name "unconnected-(IC6-GPA6-Pad27)") (class "Default")
      (node (ref "IC6") (pin "27") (pinfunction "GPA6_27") (pintype "bidirectional"))
    )
    (net (code "74") (name "unconnected-(IC6-GPA7-Pad28)") (class "Default")
      (node (ref "IC6") (pin "28") (pinfunction "GPA7_28") (pintype "bidirectional"))
    )
    (net (code "75") (name "unconnected-(IC6-GPB6-Pad7)") (class "Default")
      (node (ref "IC6") (pin "7") (pinfunction "GPB6_7") (pintype "bidirectional"))
    )
    (net (code "76") (name "unconnected-(IC6-GPB7-Pad8)") (class "Default")
      (node (ref "IC6") (pin "8") (pinfunction "GPB7_8") (pintype "bidirectional"))
    )
    (net (code "77") (name "unconnected-(IC6-INTA-Pad20)") (class "Default")
      (node (ref "IC6") (pin "20") (pinfunction "INTA_20") (pintype "output"))
    )
    (net (code "78") (name "unconnected-(IC6-INTB-Pad19)") (class "Default")
      (node (ref "IC6") (pin "19") (pinfunction "INTB_19") (pintype "output"))
    )
    (net (code "79") (name "unconnected-(IC8-PB6(OC1B{slash}OC4B{slash}ADC13)-Pad30)") (class "Default")
      (node (ref "IC8") (pin "30") (pinfunction "PB6(OC1B/OC4B/ADC13)_30") (pintype "bidirectional"))
    )
    (net (code "80") (name "unconnected-(IC8-PC6(OC3A{slash}~{OC4A})-Pad31)") (class "Default")
      (node (ref "IC8") (pin "31") (pinfunction "PC6(OC3A/~{OC4A})_31") (pintype "bidirectional"))
    )
    (net (code "81") (name "unconnected-(IC8-PC7(ICP3{slash}CLK0{slash}OC4A)-Pad32)") (class "Default")
      (node (ref "IC8") (pin "32") (pinfunction "PC7(ICP3/CLK0/OC4A)_32") (pintype "bidirectional"))
    )
    (net (code "82") (name "unconnected-(IC8-PE6(INT.6{slash}AIN0)-Pad1)") (class "Default")
      (node (ref "IC8") (pin "1") (pinfunction "PE6(INT.6/AIN0)_1") (pintype "bidirectional"))
    )
    (net (code "83") (name "unconnected-(IC8-PF0(ADC0)-Pad41)") (class "Default")
      (node (ref "IC8") (pin "41") (pinfunction "PF0(ADC0)_41") (pintype "bidirectional"))
    )
    (net (code "84") (name "unconnected-(IC8-PF1(ADC1)-Pad40)") (class "Default")
      (node (ref "IC8") (pin "40") (pinfunction "PF1(ADC1)_40") (pintype "bidirectional"))
    )
    (net (code "85") (name "unconnected-(IC8-PF4(ADC4{slash}TCK)-Pad39)") (class "Default")
      (node (ref "IC8") (pin "39") (pinfunction "PF4(ADC4/TCK)_39") (pintype "bidirectional"))
    )
    (net (code "86") (name "unconnected-(IC8-PF5(ADC5{slash}TMS)-Pad38)") (class "Default")
      (node (ref "IC8") (pin "38") (pinfunction "PF5(ADC5/TMS)_38") (pintype "bidirectional"))
    )
    (net (code "87") (name "unconnected-(IC8-PF6(ADC6{slash}TDO)-Pad37)") (class "Default")
      (node (ref "IC8") (pin "37") (pinfunction "PF6(ADC6/TDO)_37") (pintype "bidirectional"))
    )
    (net (code "88") (name "unconnected-(IC8-PF7(ADC7(TDI)-Pad36)") (class "Default")
      (node (ref "IC8") (pin "36") (pinfunction "PF7(ADC7(TDI)_36") (pintype "bidirectional"))
    )
    (net (code "89") (name "unconnected-(JK1-PadRSH)") (class "Default")
      (node (ref "JK1") (pin "RSH") (pinfunction "RSH_RSH") (pintype "bidirectional"))
    )
    (net (code "90") (name "unconnected-(JK2-PadRSH)") (class "Default")
      (node (ref "JK2") (pin "RSH") (pinfunction "RSH_RSH") (pintype "bidirectional"))
    )
    (net (code "91") (name "unconnected-(JK3-PadRSH)") (class "Default")
      (node (ref "JK3") (pin "RSH") (pinfunction "RSH_RSH") (pintype "bidirectional"))
    )
    (net (code "92") (name "unconnected-(U$1-DIO0-Pad20)") (class "Default")
      (node (ref "U$1") (pin "20") (pinfunction "DIO0_20") (pintype "bidirectional"))
    )
    (net (code "93") (name "unconnected-(U$1-DIO1-Pad19)") (class "Default")
      (node (ref "U$1") (pin "19") (pinfunction "DIO1_19") (pintype "bidirectional"))
    )
    (net (code "94") (name "unconnected-(U$1-DIO2-Pad18)") (class "Default")
      (node (ref "U$1") (pin "18") (pinfunction "DIO2_18") (pintype "bidirectional"))
    )
    (net (code "95") (name "unconnected-(U$1-DIO3-Pad17)") (class "Default")
      (node (ref "U$1") (pin "17") (pinfunction "DIO3_17") (pintype "bidirectional"))
    )
    (net (code "96") (name "unconnected-(U$1-DIO4-Pad11)") (class "Default")
      (node (ref "U$1") (pin "11") (pinfunction "DIO4_11") (pintype "bidirectional"))
    )
    (net (code "97") (name "unconnected-(U$1-DIO5-Pad15)") (class "Default")
      (node (ref "U$1") (pin "15") (pinfunction "DIO5_15") (pintype "bidirectional"))
    )
    (net (code "98") (name "unconnected-(U$1-DIO9-Pad13)") (class "Default")
      (node (ref "U$1") (pin "13") (pinfunction "DIO9_13") (pintype "bidirectional"))
    )
    (net (code "99") (name "unconnected-(U$1-DIO11-Pad7)") (class "Default")
      (node (ref "U$1") (pin "7") (pinfunction "DIO11_7") (pintype "bidirectional"))
    )
    (net (code "100") (name "unconnected-(U$1-DIO12-Pad4)") (class "Default")
      (node (ref "U$1") (pin "4") (pinfunction "DIO12_4") (pintype "bidirectional"))
    )
    (net (code "101") (name "unconnected-(U$1-RES-Pad8)") (class "Default")
      (node (ref "U$1") (pin "8") (pinfunction "RES_8") (pintype "bidirectional"))
    )
    (net (code "102") (name "unconnected-(U$1-RES-Pad14)") (class "Default")
      (node (ref "U$1") (pin "14") (pinfunction "RES_14") (pintype "bidirectional"))
    )
  )
)
